# 5V-to-12V-Converter-alt.net
KiCad netlist of a schematic drawn in EAGLE
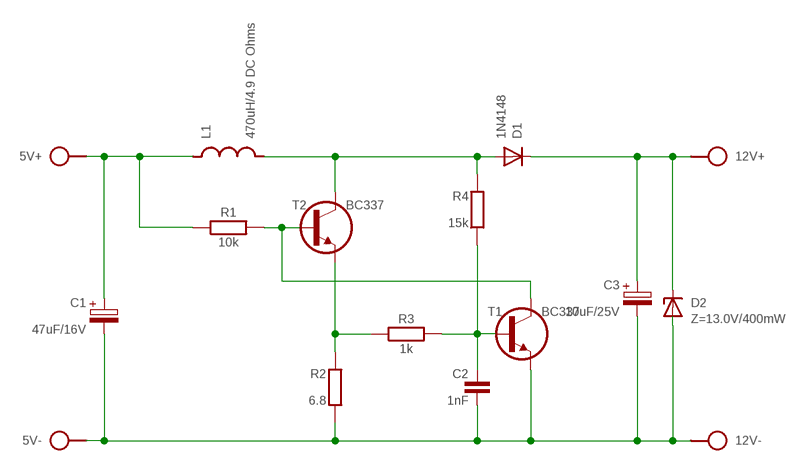
[diagram p0: schematic, sheet 1]

(export (version "E")
  (design (tool "Eeschema 10.0.6"))
  (components
    (comp (ref "5V")
      (value "SPAD+--+")
      (footprint "eagle-import:SPAD-+")
      (libsource (lib "eagle-import") (part "SPAD+--+"))
    )
    (comp (ref "12V")
      (value "SPAD+--+")
      (footprint "eagle-import:SPAD-+")
      (libsource (lib "eagle-import") (part "SPAD+--+"))
    )
    (comp (ref "C1")
      (value "47uF/16V")
      (footprint "eagle-import:E2.5-4_V")
      (libsource (lib "eagle-import") (part "CPOLE2,5-4/V"))
    )
    (comp (ref "C2")
      (value "1nF")
      (footprint "eagle-import:C050-020X036")
      (libsource (lib "eagle-import") (part "C050-020X036"))
    )
    (comp (ref "C3")
      (value "10uF/25V")
      (footprint "eagle-import:E2.5-4_V")
      (libsource (lib "eagle-import") (part "CPOLE2,5-4/V"))
    )
    (comp (ref "D1")
      (value "1N4148")
      (footprint "eagle-import:DO35-2_54A")
      (libsource (lib "eagle-import") (part "1N414835-2.54A"))
    )
    (comp (ref "D2")
      (value "Z=13.0V/400mW")
      (footprint "eagle-import:DO34Z12V")
      (libsource (lib "eagle-import") (part "Z-DIODE34Z12V"))
    )
    (comp (ref "L1")
      (value "470uH/4.9 DC Ohms")
      (footprint "eagle-import:ED16-X")
      (libsource (lib "eagle-import") (part "L-SHORTED16-X"))
    )
    (comp (ref "R1")
      (value "10k")
      (footprint "eagle-import:0204_10")
      (libsource (lib "eagle-import") (part "R-H0204/10"))
    )
    (comp (ref "R2")
      (value "6.8")
      (footprint "eagle-import:0204_10")
      (libsource (lib "eagle-import") (part "R0204/10"))
    )
    (comp (ref "R3")
      (value "1k")
      (footprint "eagle-import:0204_10")
      (libsource (lib "eagle-import") (part "R-H0204/10"))
    )
    (comp (ref "R4")
      (value "15k")
      (footprint "eagle-import:0204_10")
      (libsource (lib "eagle-import") (part "R0204/10"))
    )
    (comp (ref "T1")
      (value "BC337")
      (footprint "eagle-import:TO92-CBE")
      (libsource (lib "eagle-import") (part "BC337CBE"))
    )
    (comp (ref "T2")
      (value "BC337")
      (footprint "eagle-import:TO92-CBE")
      (libsource (lib "eagle-import") (part "BC337CBE"))
    )
  )
  (nets
    (net (code "1") (name "/N$18") (class "Default")
      (node (ref "5V") (pin "2") (pinfunction "P$1_2") (pintype "passive"))
      (node (ref "C1") (pin "+") (pinfunction "+_+") (pintype "passive"))
      (node (ref "D1") (pin "A") (pinfunction "A_A") (pintype "passive"))
      (node (ref "L1") (pin "1") (pinfunction "1_1") (pintype "passive"))
      (node (ref "L1") (pin "2") (pinfunction "2_2") (pintype "passive"))
      (node (ref "R1") (pin "1") (pinfunction "1_1") (pintype "passive"))
      (node (ref "R4") (pin "2") (pinfunction "1_2") (pintype "passive"))
      (node (ref "T2") (pin "C") (pinfunction "C_C") (pintype "passive"))
    )
    (net (code "2") (name "Net-(12VA-P$1)") (class "Default")
      (node (ref "12V") (pin "2") (pinfunction "P$1_2") (pintype "passive"))
      (node (ref "C3") (pin "+") (pinfunction "+_+") (pintype "passive"))
      (node (ref "D1") (pin "C") (pinfunction "C_C") (pintype "passive"))
      (node (ref "D2") (pin "C") (pinfunction "C_C") (pintype "passive"))
    )
    (net (code "3") (name "Net-(12VB-P$1)") (class "Default")
      (node (ref "12V") (pin "1") (pinfunction "P$1_1") (pintype "passive"))
      (node (ref "5V") (pin "1") (pinfunction "P$1_1") (pintype "passive"))
      (node (ref "C1") (pin "-") (pinfunction "-_-") (pintype "passive"))
      (node (ref "C2") (pin "2") (pinfunction "2_2") (pintype "passive"))
      (node (ref "C3") (pin "-") (pinfunction "-_-") (pintype "passive"))
      (node (ref "D2") (pin "A") (pinfunction "A_A") (pintype "passive"))
      (node (ref "R2") (pin "1") (pinfunction "2_1") (pintype "passive"))
      (node (ref "T1") (pin "E") (pinfunction "E_E") (pintype "passive"))
    )
    (net (code "4") (name "Net-(R1-Pad2)") (class "Default")
      (node (ref "R1") (pin "2") (pinfunction "2_2") (pintype "passive"))
      (node (ref "T1") (pin "C") (pinfunction "C_C") (pintype "passive"))
      (node (ref "T2") (pin "B") (pinfunction "B_B") (pintype "passive"))
    )
    (net (code "5") (name "Net-(R2-1)") (class "Default")
      (node (ref "R2") (pin "2") (pinfunction "1_2") (pintype "passive"))
      (node (ref "R3") (pin "1") (pinfunction "1_1") (pintype "passive"))
      (node (ref "T2") (pin "E") (pinfunction "E_E") (pintype "passive"))
    )
    (net (code "6") (name "Net-(R4-2)") (class "Default")
      (node (ref "C2") (pin "1") (pinfunction "1_1") (pintype "passive"))
      (node (ref "R3") (pin "2") (pinfunction "2_2") (pintype "passive"))
      (node (ref "R4") (pin "1") (pinfunction "2_1") (pintype "passive"))
      (node (ref "T1") (pin "B") (pinfunction "B_B") (pintype "passive"))
    )
  )
)
